# attiny85nightlight.net
KiCad netlist of a schematic drawn in EAGLE
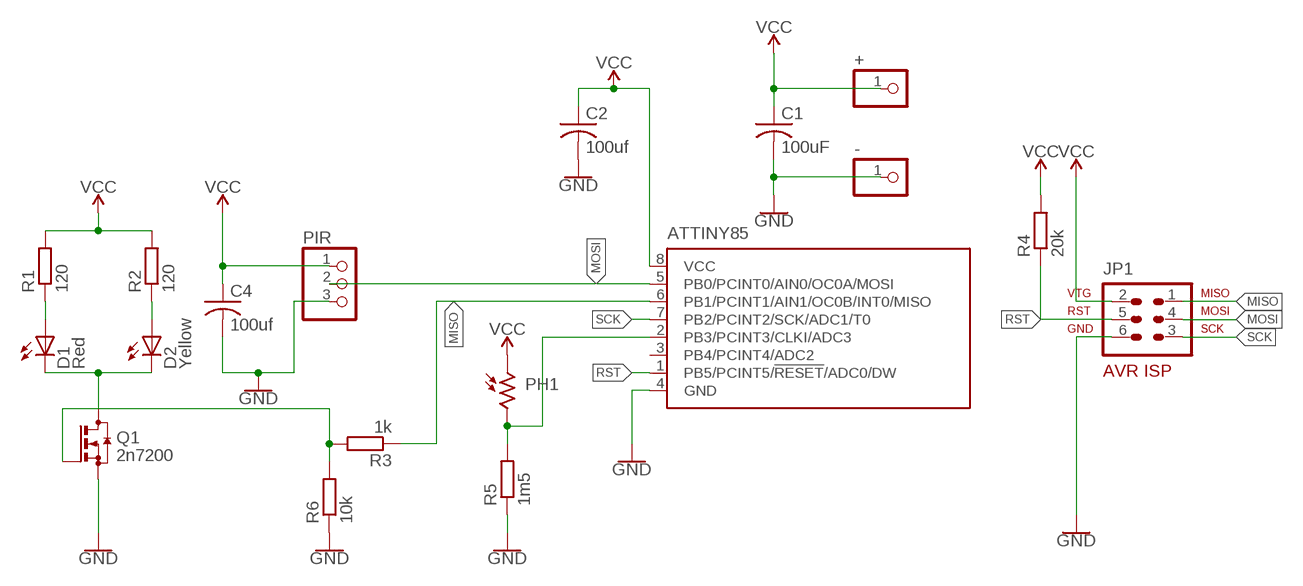
[diagram p0: schematic, sheet 1]

(export (version "E")
  (design (tool "Eeschema 10.0.6"))
  (components
    (comp (ref "+")
      (value "PINHD-1X1")
      (footprint "eagle-import:1X01")
      (libsource (lib "eagle-import") (part "PINHD-1X1"))
    )
    (comp (ref "-")
      (value "PINHD-1X1")
      (footprint "eagle-import:1X01")
      (libsource (lib "eagle-import") (part "PINHD-1X1"))
    )
    (comp (ref "ATTINY85")
      (value "TINY13-20SU")
      (footprint "eagle-import:8S2")
      (fields (field (name "MPN") "ATTINY13-20SU"))
      (libsource (lib "eagle-import") (part "TINY13SU-20"))
    )
    (comp (ref "C1")
      (value "100uF")
      (footprint "eagle-import:C0805")
      (libsource (lib "eagle-import") (part "C-USC0805"))
    )
    (comp (ref "C2")
      (value "100uf")
      (footprint "eagle-import:C0805")
      (libsource (lib "eagle-import") (part "C-USC0805"))
    )
    (comp (ref "C4")
      (value "100uf")
      (footprint "eagle-import:C0805")
      (libsource (lib "eagle-import") (part "C-USC0805"))
    )
    (comp (ref "D1")
      (value "Red")
      (footprint "eagle-import:LED5MM")
      (libsource (lib "eagle-import") (part "LED5MM"))
    )
    (comp (ref "D2")
      (value "Yellow")
      (footprint "eagle-import:LED5MM")
      (libsource (lib "eagle-import") (part "LED5MM"))
    )
    (comp (ref "JP1")
      (value "AVR-ISP-6")
      (footprint "eagle-import:AVR-ISP-6")
      (libsource (lib "eagle-import") (part "AVR-ISP-6"))
    )
    (comp (ref "PH1")
      (value "A1050_09")
      (footprint "eagle-import:T0-46-A10XX")
      (libsource (lib "eagle-import") (part "A1050_09"))
    )
    (comp (ref "PIR")
      (value "PINHD-1X3")
      (footprint "eagle-import:1X03")
      (libsource (lib "eagle-import") (part "PINHD-1X3"))
    )
    (comp (ref "Q1")
      (value "2n7200")
      (footprint "eagle-import:SOT23")
      (libsource (lib "eagle-import") (part "BSS123"))
    )
    (comp (ref "R1")
      (value "120")
      (footprint "eagle-import:R0805")
      (libsource (lib "eagle-import") (part "R-EU_R0805"))
    )
    (comp (ref "R2")
      (value "120")
      (footprint "eagle-import:R0805")
      (libsource (lib "eagle-import") (part "R-EU_R0805"))
    )
    (comp (ref "R3")
      (value "1k")
      (footprint "eagle-import:R0805")
      (libsource (lib "eagle-import") (part "R-EU_R0805"))
    )
    (comp (ref "R4")
      (value "20k")
      (footprint "eagle-import:R0805")
      (libsource (lib "eagle-import") (part "R-EU_R0805"))
    )
    (comp (ref "R5")
      (value "1m5")
      (footprint "eagle-import:R0805")
      (libsource (lib "eagle-import") (part "R-EU_R0805"))
    )
    (comp (ref "R6")
      (value "10k")
      (footprint "eagle-import:R0805")
      (libsource (lib "eagle-import") (part "R-EU_R0805"))
    )
  )
  (nets
    (net (code "1") (name "GND") (class "Default")
      (node (ref "-") (pin "1") (pinfunction "1_1") (pintype "passive"))
      (node (ref "ATTINY85") (pin "4") (pinfunction "GND_4") (pintype "power_in"))
      (node (ref "C1") (pin "2") (pinfunction "2_2") (pintype "passive"))
      (node (ref "C2") (pin "2") (pinfunction "2_2") (pintype "passive"))
      (node (ref "C4") (pin "2") (pinfunction "2_2") (pintype "passive"))
      (node (ref "JP1") (pin "6") (pinfunction "6_6") (pintype "passive"))
      (node (ref "PIR") (pin "3") (pinfunction "3_3") (pintype "passive"))
      (node (ref "Q1") (pin "2") (pinfunction "S_2") (pintype "passive"))
      (node (ref "R5") (pin "1") (pinfunction "1_1") (pintype "passive"))
      (node (ref "R6") (pin "1") (pinfunction "1_1") (pintype "passive"))
    )
    (net (code "2") (name "MISO") (class "Default")
      (node (ref "ATTINY85") (pin "6") (pinfunction "PB1/PCINT1/AIN1/OC0B/INT0/MISO_6") (pintype "bidirectional"))
      (node (ref "JP1") (pin "1") (pinfunction "1_1") (pintype "passive"))
      (node (ref "R3") (pin "1") (pinfunction "1_1") (pintype "passive"))
    )
    (net (code "3") (name "MOSI") (class "Default")
      (node (ref "ATTINY85") (pin "5") (pinfunction "PB0/PCINT0/AIN0/OC0A/MOSI_5") (pintype "bidirectional"))
      (node (ref "JP1") (pin "4") (pinfunction "4_4") (pintype "passive"))
      (node (ref "PIR") (pin "2") (pinfunction "2_2") (pintype "passive"))
    )
    (net (code "4") (name "Net-(ATTINY85-PB3{slash}PCINT3{slash}CLKI{slash}ADC3)") (class "Default")
      (node (ref "ATTINY85") (pin "2") (pinfunction "PB3/PCINT3/CLKI/ADC3_2") (pintype "bidirectional"))
      (node (ref "PH1") (pin "2") (pinfunction "2_2") (pintype "passive"))
      (node (ref "R5") (pin "2") (pinfunction "2_2") (pintype "passive"))
    )
    (net (code "5") (name "Net-(D1-C)") (class "Default")
      (node (ref "D1") (pin "K") (pinfunction "C_K") (pintype "passive"))
      (node (ref "D2") (pin "K") (pinfunction "C_K") (pintype "passive"))
      (node (ref "Q1") (pin "3") (pinfunction "D_3") (pintype "passive"))
    )
    (net (code "6") (name "Net-(D1-PadA)") (class "Default")
      (node (ref "D1") (pin "A") (pinfunction "A_A") (pintype "passive"))
      (node (ref "R1") (pin "1") (pinfunction "1_1") (pintype "passive"))
    )
    (net (code "7") (name "Net-(D2-PadA)") (class "Default")
      (node (ref "D2") (pin "A") (pinfunction "A_A") (pintype "passive"))
      (node (ref "R2") (pin "1") (pinfunction "1_1") (pintype "passive"))
    )
    (net (code "8") (name "Net-(Q1-G)") (class "Default")
      (node (ref "Q1") (pin "1") (pinfunction "G_1") (pintype "passive"))
      (node (ref "R3") (pin "2") (pinfunction "2_2") (pintype "passive"))
      (node (ref "R6") (pin "2") (pinfunction "2_2") (pintype "passive"))
    )
    (net (code "9") (name "RST") (class "Default")
      (node (ref "ATTINY85") (pin "1") (pinfunction "PB5/PCINT5/~{RESET}/ADC0/DW_1") (pintype "bidirectional"))
      (node (ref "JP1") (pin "5") (pinfunction "5_5") (pintype "passive"))
      (node (ref "R4") (pin "1") (pinfunction "1_1") (pintype "passive"))
    )
    (net (code "10") (name "SCK") (class "Default")
      (node (ref "ATTINY85") (pin "7") (pinfunction "PB2/PCINT2/SCK/ADC1/T0_7") (pintype "bidirectional"))
      (node (ref "JP1") (pin "3") (pinfunction "3_3") (pintype "passive"))
    )
    (net (code "11") (name "VCC") (class "Default")
      (node (ref "+") (pin "1") (pinfunction "1_1") (pintype "passive"))
      (node (ref "ATTINY85") (pin "8") (pinfunction "VCC_8") (pintype "power_in"))
      (node (ref "C1") (pin "1") (pinfunction "1_1") (pintype "passive"))
      (node (ref "C2") (pin "1") (pinfunction "1_1") (pintype "passive"))
      (node (ref "C4") (pin "1") (pinfunction "1_1") (pintype "passive"))
      (node (ref "JP1") (pin "2") (pinfunction "2_2") (pintype "passive"))
      (node (ref "PH1") (pin "1") (pinfunction "1_1") (pintype "passive"))
      (node (ref "PIR") (pin "1") (pinfunction "1_1") (pintype "passive"))
      (node (ref "R1") (pin "2") (pinfunction "2_2") (pintype "passive"))
      (node (ref "R2") (pin "2") (pinfunction "2_2") (pintype "passive"))
      (node (ref "R4") (pin "2") (pinfunction "2_2") (pintype "passive"))
    )
    (net (code "12") (name "unconnected-(ATTINY85-PB4{slash}PCINT4{slash}ADC2-Pad3)") (class "Default")
      (node (ref "ATTINY85") (pin "3") (pinfunction "PB4/PCINT4/ADC2_3") (pintype "bidirectional"))
    )
  )
)
